# Display.net
KiCad netlist of a schematic drawn in Altium Designer
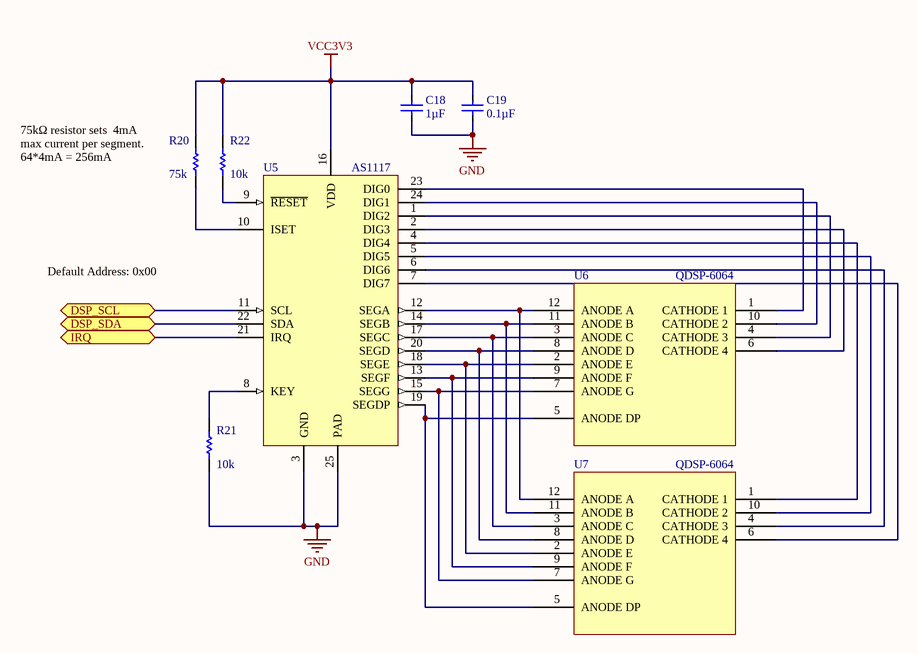
[diagram p0: Display.SchDoc]

(export (version "E")
  (design (tool "Eeschema 10.0.6"))
  (components
    (comp (ref "C18")
      (value "1µF")
      (footprint "CAPC1005X50L25N")
      (description "CAP CER 1UF 6.3V X7R 0402")
      (fields
        (field (name "MANUFACTURER") "Murata Electronics North America")
        (field (name "MANUFACTURER PART NUMBER") "GRM155R70J105KA12D")
      )
      (libsource (lib "mechanart_oshw") (part "CapSMT"))
    )
    (comp (ref "C19")
      (value "0.1µF")
      (footprint "CAPC1005X50L25N")
      (description "CAP CER 0.1UF 50V X7R 0402")
      (fields
        (field (name "MANUFACTURER") "Murata Electronics North America")
        (field (name "MANUFACTURER PART NUMBER") "GRM155R71H104KE14D")
      )
      (libsource (lib "mechanart_oshw") (part "CapSMT"))
    )
    (comp (ref "R20")
      (value "75k")
      (footprint "RESC1005X40L25N")
      (description "RES SMD 75K OHM 1% 1/10W 0402")
      (fields
        (field (name "MANUFACTURER") "Panasonic Electronic Components")
        (field (name "MANUFACTURER PART NUMBER") "ERJ-2RKF7502X")
      )
      (libsource (lib "mechanart_oshw") (part "ResSMT"))
    )
    (comp (ref "R21")
      (value "10k")
      (footprint "RESC1005X40L25N")
      (description "RES SMD 10K OHM 5% 1/16W 0402")
      (fields
        (field (name "MANUFACTURER") "Vishay Dale")
        (field (name "MANUFACTURER PART NUMBER") "CRCW040210K0JNED")
      )
      (libsource (lib "mechanart_oshw") (part "ResSMT"))
    )
    (comp (ref "R22")
      (value "10k")
      (footprint "RESC1005X40L25N")
      (description "RES SMD 10K OHM 5% 1/16W 0402")
      (fields
        (field (name "MANUFACTURER") "Vishay Dale")
        (field (name "MANUFACTURER PART NUMBER") "CRCW040210K0JNED")
      )
      (libsource (lib "mechanart_oshw") (part "ResSMT"))
    )
    (comp (ref "U5")
      (value "AS1117")
      (footprint "PQFN50P400X400X60-25T290X290L")
      (description "IC DRIVER 64LED MOBILE 24-TQFN")
      (fields (field (name "MANUFACTURER") "ams") (field (name "MANUFACTURER PART NUMBER") "AS1117-BQFT"))
      (libsource (lib "mechanart_oshw") (part "AS1117"))
    )
    (comp (ref "U6")
      (value "QDSP-6064")
      (footprint "DIP762W51P254L1537H483Q12_SMT")
      (description "HP 4-Digit LED 7-Segment Bubble Display")
      (fields (field (name "MANUFACTURER") "HP"))
      (libsource (lib "mechanart_oshw") (part "QDSP-6064"))
    )
    (comp (ref "U7")
      (value "QDSP-6064")
      (footprint "DIP762W51P254L1537H483Q12_SMT")
      (description "HP 4-Digit LED 7-Segment Bubble Display")
      (fields (field (name "MANUFACTURER") "HP"))
      (libsource (lib "mechanart_oshw") (part "QDSP-6064"))
    )
  )
  (nets
    (net (code "1") (name "/DSP_SCL") (class "Default")
      (node (ref "U5") (pin "11") (pinfunction "SCL_11") (pintype "input"))
    )
    (net (code "2") (name "/DSP_SDA") (class "Default")
      (node (ref "U5") (pin "22") (pinfunction "SDA_22") (pintype "open_collector"))
    )
    (net (code "3") (name "/IRQ") (class "Default")
      (node (ref "U5") (pin "21") (pinfunction "IRQ_21") (pintype "open_collector"))
    )
    (net (code "4") (name "GND") (class "Default")
      (node (ref "C18") (pin "2") (pinfunction "2_2") (pintype "passive"))
      (node (ref "C19") (pin "2") (pinfunction "2_2") (pintype "passive"))
      (node (ref "R21") (pin "1") (pinfunction "1_1") (pintype "passive"))
      (node (ref "U5") (pin "25") (pinfunction "PAD_25") (pintype "power_in"))
      (node (ref "U5") (pin "3") (pinfunction "GND_3") (pintype "power_in"))
    )
    (net (code "5") (name "Net-(U5-DIG0)") (class "Default")
      (node (ref "U5") (pin "23") (pinfunction "DIG0_23") (pintype "open_collector"))
      (node (ref "U6") (pin "1") (pinfunction "CATHODE_1_1") (pintype "passive"))
    )
    (net (code "6") (name "Net-(U5-DIG1)") (class "Default")
      (node (ref "U5") (pin "24") (pinfunction "DIG1_24") (pintype "open_collector"))
      (node (ref "U6") (pin "10") (pinfunction "CATHODE_2_10") (pintype "passive"))
    )
    (net (code "7") (name "Net-(U5-DIG2)") (class "Default")
      (node (ref "U5") (pin "1") (pinfunction "DIG2_1") (pintype "open_collector"))
      (node (ref "U6") (pin "4") (pinfunction "CATHODE_3_4") (pintype "passive"))
    )
    (net (code "8") (name "Net-(U5-DIG3)") (class "Default")
      (node (ref "U5") (pin "2") (pinfunction "DIG3_2") (pintype "open_collector"))
      (node (ref "U6") (pin "6") (pinfunction "CATHODE_4_6") (pintype "passive"))
    )
    (net (code "9") (name "Net-(U5-DIG4)") (class "Default")
      (node (ref "U5") (pin "4") (pinfunction "DIG4_4") (pintype "open_collector"))
      (node (ref "U7") (pin "1") (pinfunction "CATHODE_1_1") (pintype "passive"))
    )
    (net (code "10") (name "Net-(U5-DIG5)") (class "Default")
      (node (ref "U5") (pin "5") (pinfunction "DIG5_5") (pintype "open_collector"))
      (node (ref "U7") (pin "10") (pinfunction "CATHODE_2_10") (pintype "passive"))
    )
    (net (code "11") (name "Net-(U5-DIG6)") (class "Default")
      (node (ref "U5") (pin "6") (pinfunction "DIG6_6") (pintype "open_collector"))
      (node (ref "U7") (pin "4") (pinfunction "CATHODE_3_4") (pintype "passive"))
    )
    (net (code "12") (name "Net-(U5-DIG7)") (class "Default")
      (node (ref "U5") (pin "7") (pinfunction "DIG7_7") (pintype "open_collector"))
      (node (ref "U7") (pin "6") (pinfunction "CATHODE_4_6") (pintype "passive"))
    )
    (net (code "13") (name "Net-(U5-ISET)") (class "Default")
      (node (ref "R20") (pin "1") (pinfunction "1_1") (pintype "passive"))
      (node (ref "U5") (pin "10") (pinfunction "ISET_10") (pintype "passive"))
    )
    (net (code "14") (name "Net-(U5-KEY)") (class "Default")
      (node (ref "R21") (pin "2") (pinfunction "2_2") (pintype "passive"))
      (node (ref "U5") (pin "8") (pinfunction "KEY_8") (pintype "input"))
    )
    (net (code "15") (name "Net-(U5-SEGA)") (class "Default")
      (node (ref "U5") (pin "12") (pinfunction "SEGA_12") (pintype "output"))
      (node (ref "U6") (pin "12") (pinfunction "ANODE_A_12") (pintype "passive"))
      (node (ref "U7") (pin "12") (pinfunction "ANODE_A_12") (pintype "passive"))
    )
    (net (code "16") (name "Net-(U5-SEGB)") (class "Default")
      (node (ref "U5") (pin "14") (pinfunction "SEGB_14") (pintype "output"))
      (node (ref "U6") (pin "11") (pinfunction "ANODE_B_11") (pintype "passive"))
      (node (ref "U7") (pin "11") (pinfunction "ANODE_B_11") (pintype "passive"))
    )
    (net (code "17") (name "Net-(U5-SEGC)") (class "Default")
      (node (ref "U5") (pin "17") (pinfunction "SEGC_17") (pintype "output"))
      (node (ref "U6") (pin "3") (pinfunction "ANODE_C_3") (pintype "passive"))
      (node (ref "U7") (pin "3") (pinfunction "ANODE_C_3") (pintype "passive"))
    )
    (net (code "18") (name "Net-(U5-SEGD)") (class "Default")
      (node (ref "U5") (pin "20") (pinfunction "SEGD_20") (pintype "output"))
      (node (ref "U6") (pin "8") (pinfunction "ANODE_D_8") (pintype "passive"))
      (node (ref "U7") (pin "8") (pinfunction "ANODE_D_8") (pintype "passive"))
    )
    (net (code "19") (name "Net-(U5-SEGDP)") (class "Default")
      (node (ref "U5") (pin "19") (pinfunction "SEGDP_19") (pintype "output"))
      (node (ref "U6") (pin "5") (pinfunction "ANODE_DP_5") (pintype "passive"))
      (node (ref "U7") (pin "5") (pinfunction "ANODE_DP_5") (pintype "passive"))
    )
    (net (code "20") (name "Net-(U5-SEGE)") (class "Default")
      (node (ref "U5") (pin "18") (pinfunction "SEGE_18") (pintype "output"))
      (node (ref "U6") (pin "2") (pinfunction "ANODE_E_2") (pintype "passive"))
      (node (ref "U7") (pin "2") (pinfunction "ANODE_E_2") (pintype "passive"))
    )
    (net (code "21") (name "Net-(U5-SEGF)") (class "Default")
      (node (ref "U5") (pin "13") (pinfunction "SEGF_13") (pintype "output"))
      (node (ref "U6") (pin "9") (pinfunction "ANODE_F_9") (pintype "passive"))
      (node (ref "U7") (pin "9") (pinfunction "ANODE_F_9") (pintype "passive"))
    )
    (net (code "22") (name "Net-(U5-SEGG)") (class "Default")
      (node (ref "U5") (pin "15") (pinfunction "SEGG_15") (pintype "output"))
      (node (ref "U6") (pin "7") (pinfunction "ANODE_G_7") (pintype "passive"))
      (node (ref "U7") (pin "7") (pinfunction "ANODE_G_7") (pintype "passive"))
    )
    (net (code "23") (name "Net-(U5-~{RESET})") (class "Default")
      (node (ref "R22") (pin "1") (pinfunction "1_1") (pintype "passive"))
      (node (ref "U5") (pin "9") (pinfunction "~{RESET}_9") (pintype "input"))
    )
    (net (code "24") (name "VCC3V3") (class "Default")
      (node (ref "C18") (pin "1") (pinfunction "1_1") (pintype "passive"))
      (node (ref "C19") (pin "1") (pinfunction "1_1") (pintype "passive"))
      (node (ref "R20") (pin "2") (pinfunction "2_2") (pintype "passive"))
      (node (ref "R22") (pin "2") (pinfunction "2_2") (pintype "passive"))
      (node (ref "U5") (pin "16") (pinfunction "VDD_16") (pintype "power_in"))
    )
  )
)
